# Schematic.net
KiCad netlist of a schematic drawn in EasyEDA
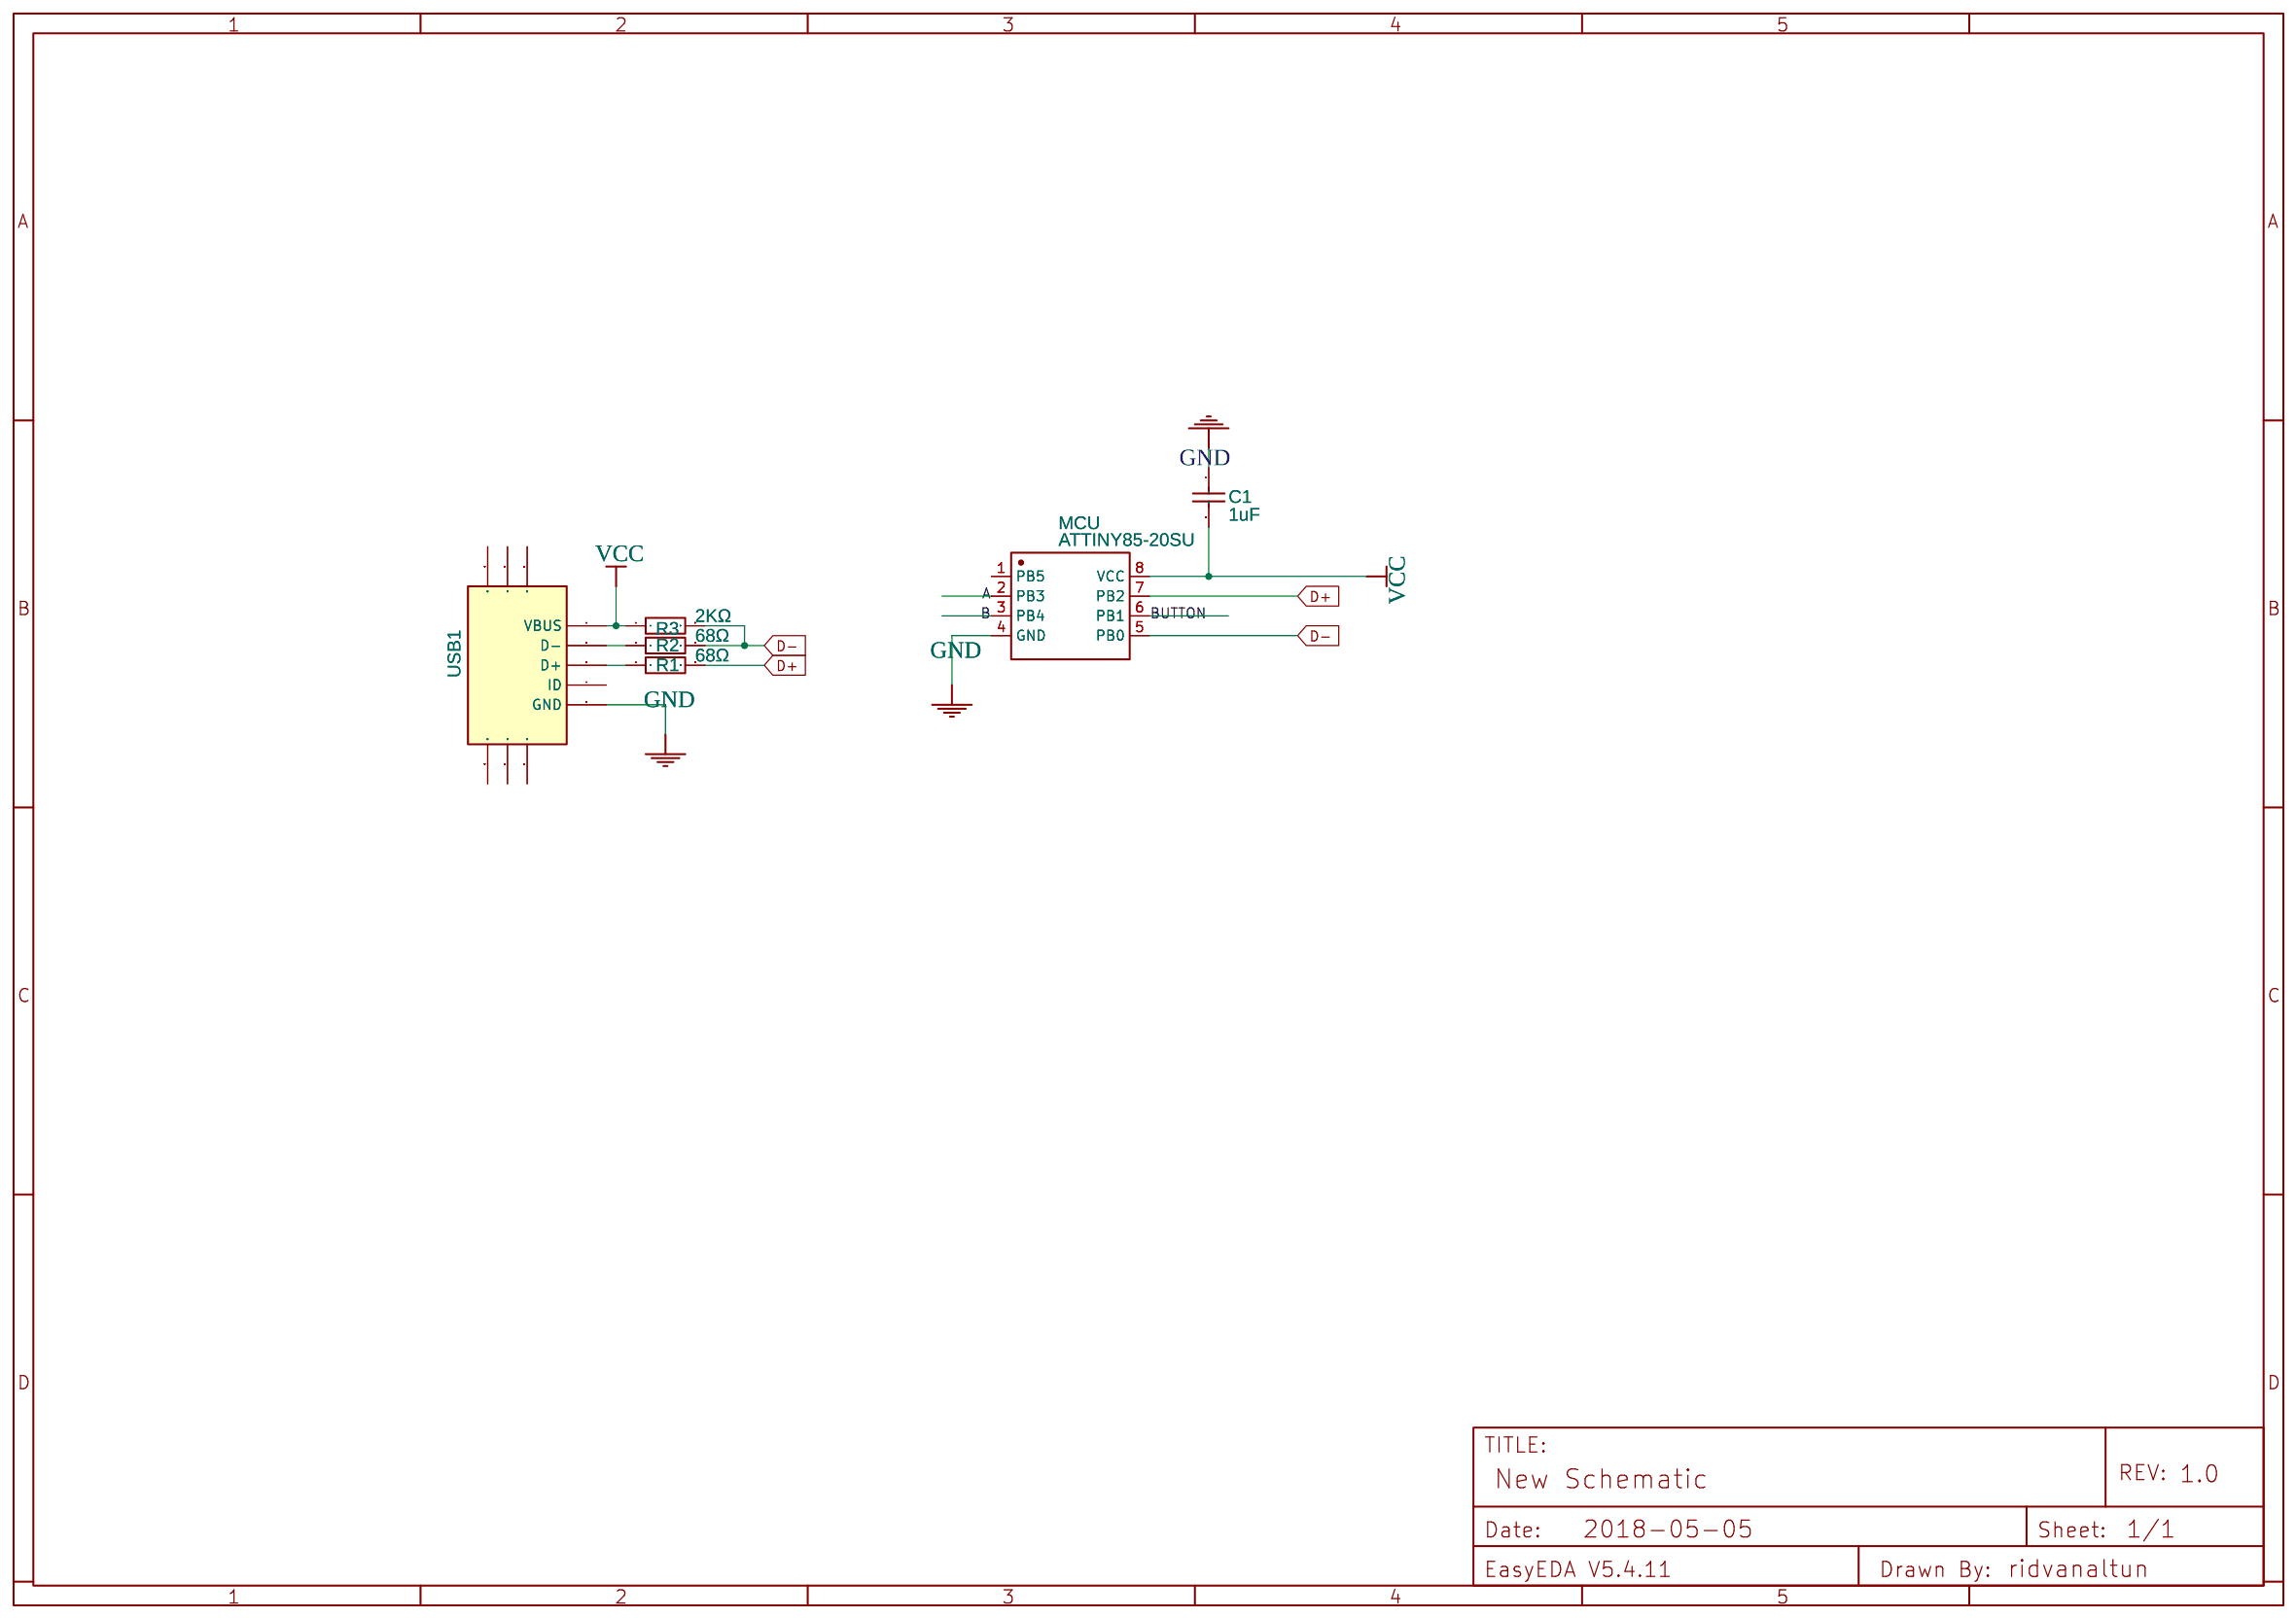
[diagram p0: MAIN]
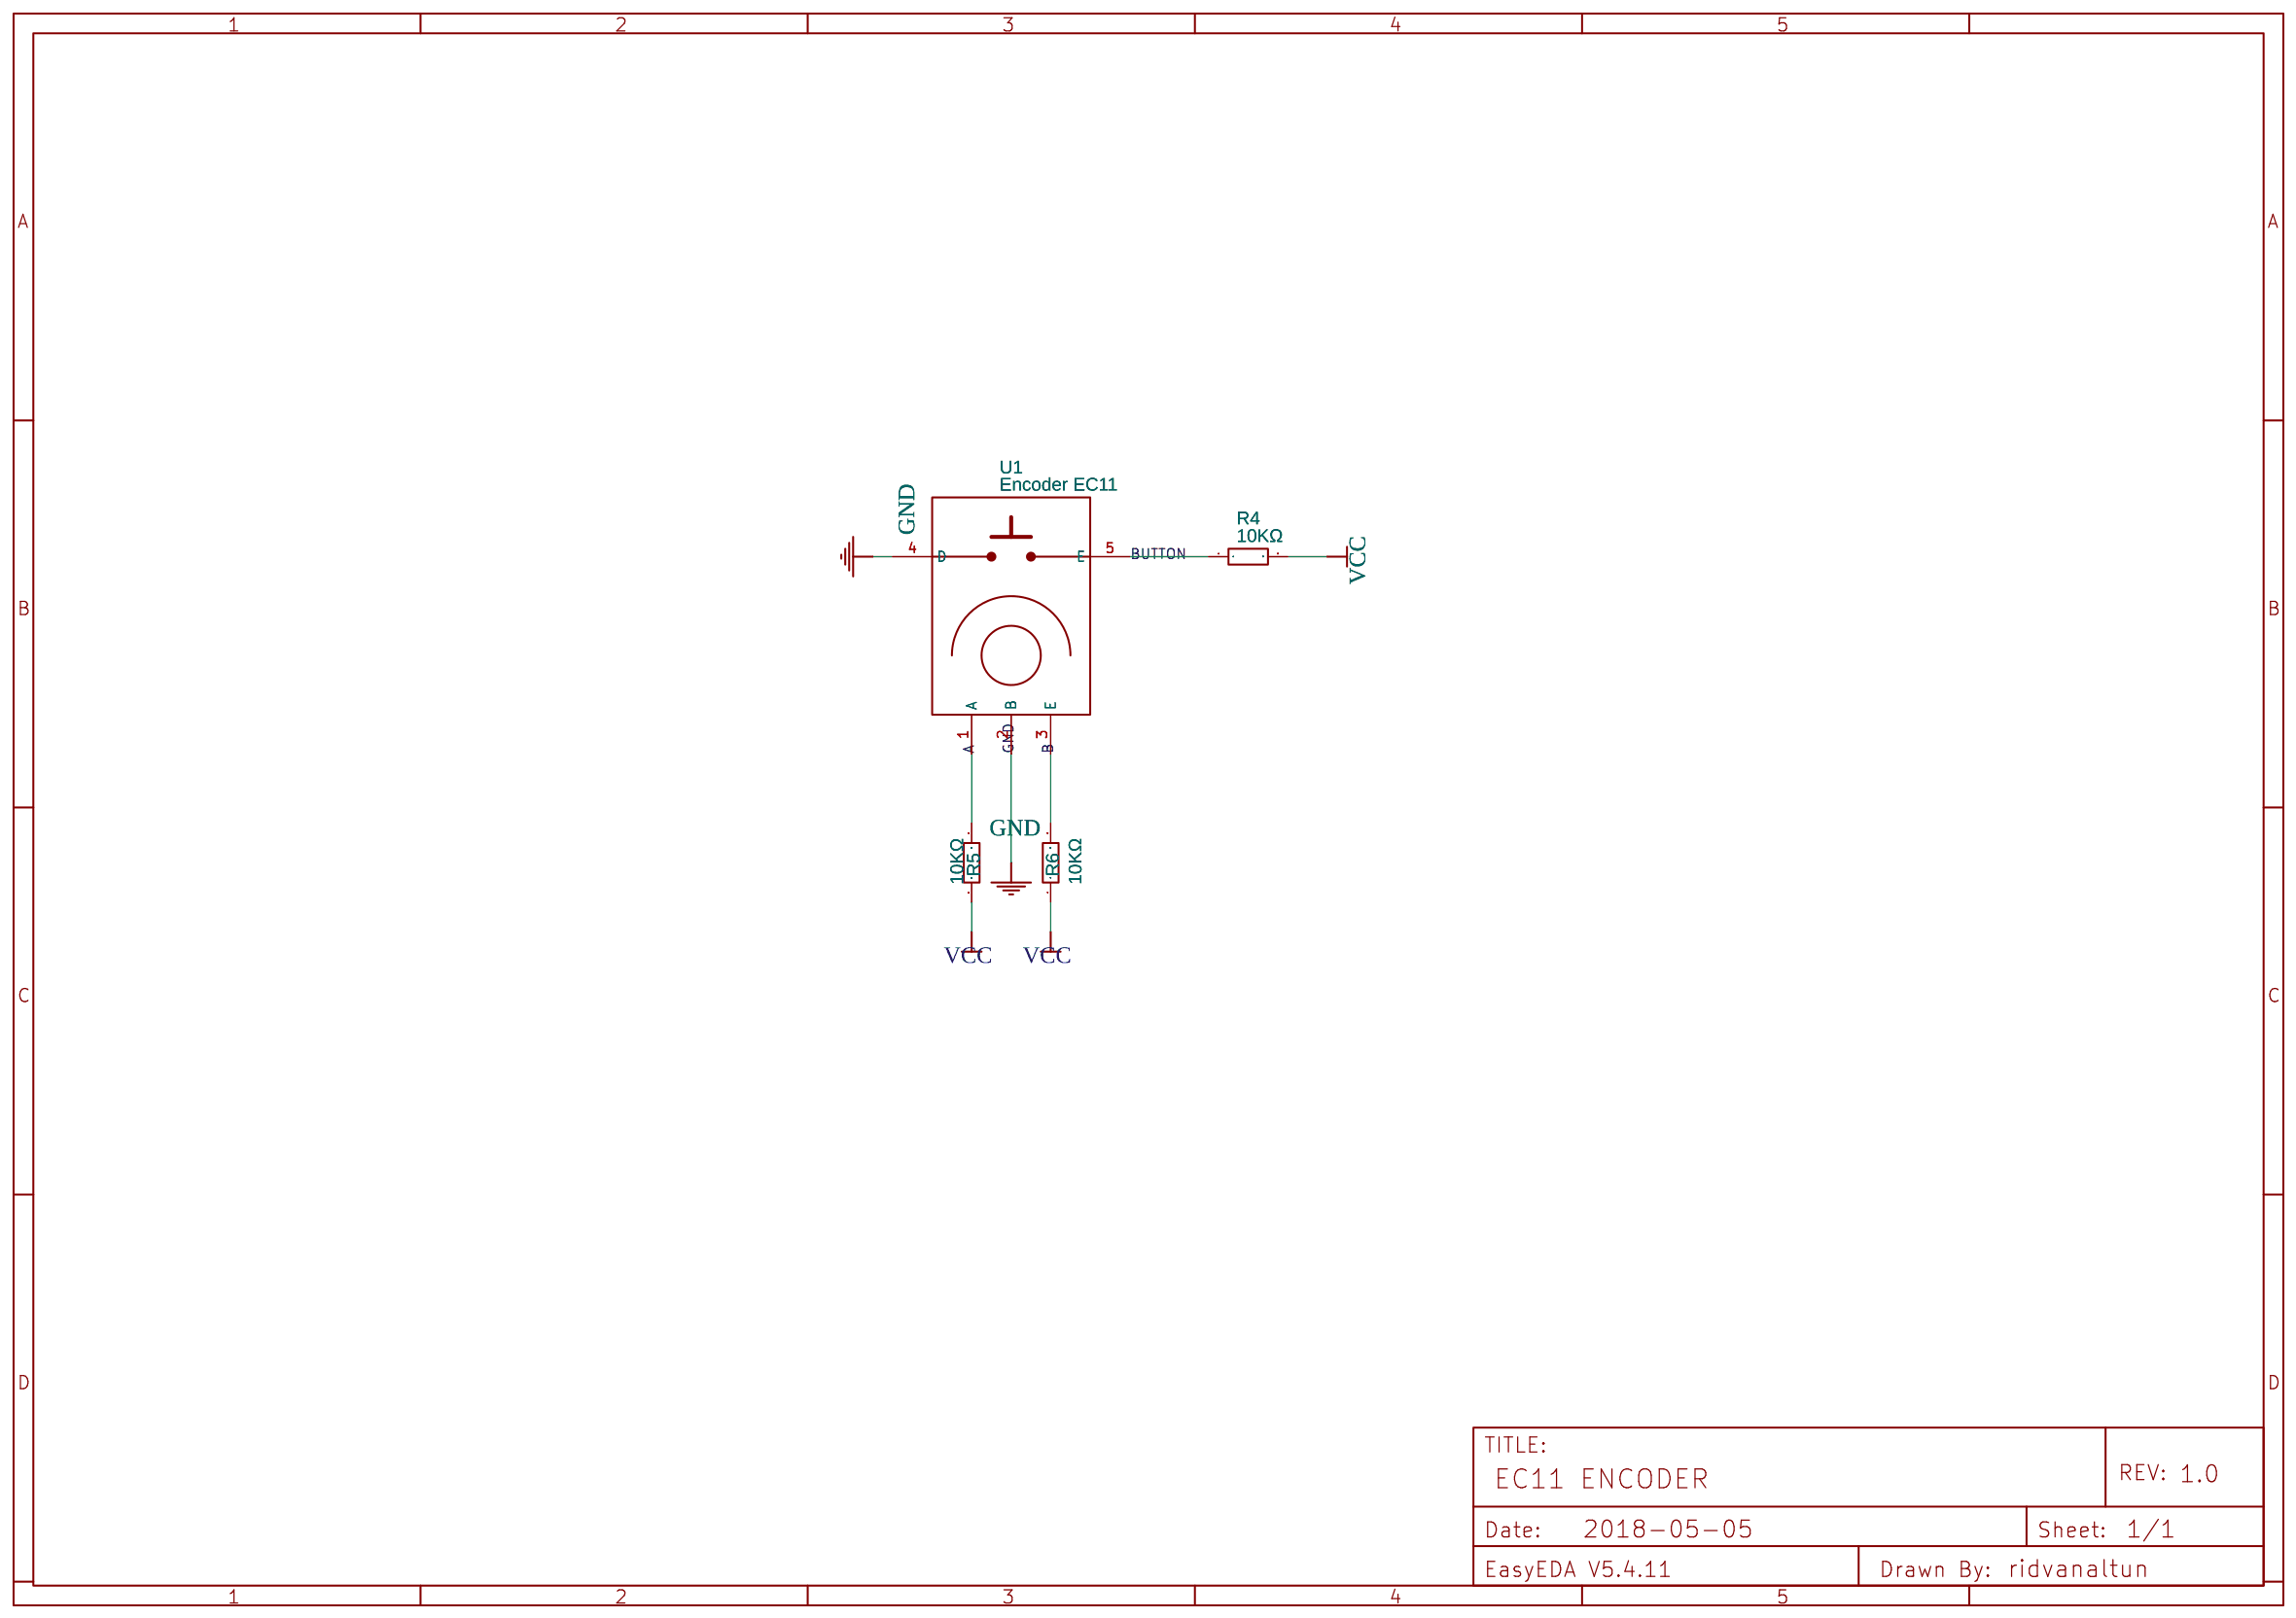
[diagram p1: ENCODER]

(export (version "E")
  (design (tool "Eeschema 10.0.6"))
  (components
    (comp (ref "C1")
      (value "1uF")
      (fields (field (name "BOM_Manufacturer Part") "NFM18PS105R0J3D"))
      (libsource (lib "") (part "NFM18PS105R0J3D"))
    )
    (comp (ref "MCU") (value "ATTINY85-20SU") (libsource (lib "") (part "Unknown_535_275")))
    (comp (ref "R1")
      (value "68Ω")
      (fields (field (name "BOM_Manufacturer Part") "0603WAF680JT5E"))
      (libsource (lib "") (part "0603WAF680JT5E"))
    )
    (comp (ref "R2")
      (value "68Ω")
      (fields (field (name "BOM_Manufacturer Part") "0603WAF680JT5E"))
      (libsource (lib "") (part "0603WAF680JT5E"))
    )
    (comp (ref "R3")
      (value "2KΩ")
      (fields (field (name "BOM_Manufacturer Part") "RTT032001FTP"))
      (libsource (lib "") (part "RTT032001FTP"))
    )
    (comp (ref "USB1")
      (value "micro 5PAll posts are not guided Flat welding")
      (libsource (lib "") (part "Unknown_250_330"))
    )
    (comp (ref "R4")
      (value "10KΩ")
      (fields (field (name "BOM_Manufacturer Part") "TC0325F1002T5E"))
      (libsource (lib "") (part "TC0325F1002T5E_2"))
    )
    (comp (ref "R5")
      (value "10KΩ")
      (fields (field (name "BOM_Manufacturer Part") "TC0325F1002T5E"))
      (libsource (lib "") (part "TC0325F1002T5E"))
    )
    (comp (ref "R6")
      (value "10KΩ")
      (fields (field (name "BOM_Manufacturer Part") "TC0325F1002T5E"))
      (libsource (lib "") (part "TC0325F1002T5E_1"))
    )
    (comp (ref "U1")
      (value "Encoder EC11")
      (fields (field (name "BOM_Manufacturer Part") "EC11"))
      (libsource (lib "") (part "Unknown_545_355"))
    )
  )
  (nets
    (net (code "1") (name "A") (class "Default")
      (node (ref "MCU") (pin "2") (pinfunction "PB3_2") (pintype "unspecified"))
      (node (ref "R5") (pin "1") (pinfunction "1_1") (pintype "unspecified"))
      (node (ref "U1") (pin "1") (pinfunction "A_1") (pintype "unspecified"))
    )
    (net (code "2") (name "B") (class "Default")
      (node (ref "MCU") (pin "3") (pinfunction "PB4_3") (pintype "unspecified"))
      (node (ref "R6") (pin "2") (pinfunction "2_2") (pintype "unspecified"))
      (node (ref "U1") (pin "3") (pinfunction "E_3") (pintype "unspecified"))
    )
    (net (code "3") (name "BUTTON") (class "Default")
      (node (ref "MCU") (pin "6") (pinfunction "PB1_6") (pintype "unspecified"))
      (node (ref "R4") (pin "1") (pinfunction "1_1") (pintype "unspecified"))
      (node (ref "U1") (pin "5") (pinfunction "E_5") (pintype "unspecified"))
    )
    (net (code "4") (name "D+") (class "Default")
      (node (ref "MCU") (pin "7") (pinfunction "PB2_7") (pintype "unspecified"))
      (node (ref "R1") (pin "2") (pinfunction "2_2") (pintype "input"))
    )
    (net (code "5") (name "D-") (class "Default")
      (node (ref "MCU") (pin "5") (pinfunction "PB0_5") (pintype "unspecified"))
      (node (ref "R2") (pin "2") (pinfunction "2_2") (pintype "input"))
      (node (ref "R3") (pin "2") (pinfunction "2_2") (pintype "input"))
    )
    (net (code "6") (name "GND") (class "Default")
      (node (ref "C1") (pin "1") (pinfunction "1_1") (pintype "input"))
      (node (ref "MCU") (pin "4") (pinfunction "GND_4") (pintype "unspecified"))
      (node (ref "U1") (pin "2") (pinfunction "B_2") (pintype "unspecified"))
      (node (ref "U1") (pin "4") (pinfunction "D_4") (pintype "unspecified"))
      (node (ref "USB1") (pin "5") (pinfunction "GND_5") (pintype "input"))
    )
    (net (code "7") (name "Net-(USB1-D+)") (class "Default")
      (node (ref "R1") (pin "1") (pinfunction "1_1") (pintype "input"))
      (node (ref "USB1") (pin "3") (pinfunction "D+_3") (pintype "input"))
    )
    (net (code "8") (name "Net-(USB1-D-)") (class "Default")
      (node (ref "R2") (pin "1") (pinfunction "1_1") (pintype "input"))
      (node (ref "USB1") (pin "2") (pinfunction "D-_2") (pintype "input"))
    )
    (net (code "9") (name "VCC") (class "Default")
      (node (ref "C1") (pin "2") (pinfunction "2_2") (pintype "input"))
      (node (ref "MCU") (pin "8") (pinfunction "VCC_8") (pintype "unspecified"))
      (node (ref "R3") (pin "1") (pinfunction "1_1") (pintype "input"))
      (node (ref "R4") (pin "2") (pinfunction "2_2") (pintype "unspecified"))
      (node (ref "R5") (pin "2") (pinfunction "2_2") (pintype "unspecified"))
      (node (ref "R6") (pin "1") (pinfunction "1_1") (pintype "unspecified"))
      (node (ref "USB1") (pin "1") (pinfunction "VBUS_1") (pintype "input"))
    )
    (net (code "10") (name "unconnected-(MCU-PB5-Pad1)") (class "Default")
      (node (ref "MCU") (pin "1") (pinfunction "PB5_1") (pintype "unspecified"))
    )
    (net (code "11") (name "unconnected-(USB1-ID-Pad4)") (class "Default")
      (node (ref "USB1") (pin "4") (pinfunction "ID_4") (pintype "input"))
    )
    (net (code "12") (name "unconnected-(USB1-MTN1-Pad0)") (class "Default")
      (node (ref "USB1") (pin "0") (pinfunction "MTN1_0") (pintype "input"))
    )
    (net (code "13") (name "unconnected-(USB1-MTN2-Pad0)") (class "Default")
      (node (ref "USB1") (pin "0") (pinfunction "MTN2_0") (pintype "input"))
    )
    (net (code "14") (name "unconnected-(USB1-MTN3-Pad0)") (class "Default")
      (node (ref "USB1") (pin "0") (pinfunction "MTN3_0") (pintype "input"))
    )
    (net (code "15") (name "unconnected-(USB1-MTN4-Pad0)") (class "Default")
      (node (ref "USB1") (pin "0") (pinfunction "MTN4_0") (pintype "input"))
    )
    (net (code "16") (name "unconnected-(USB1-MTN5-Pad0)") (class "Default")
      (node (ref "USB1") (pin "0") (pinfunction "MTN5_0") (pintype "input"))
    )
    (net (code "17") (name "unconnected-(USB1-MTN6-Pad0)") (class "Default")
      (node (ref "USB1") (pin "0") (pinfunction "MTN6_0") (pintype "input"))
    )
  )
)
